# power.net
KiCad netlist of a schematic drawn in Altium Designer
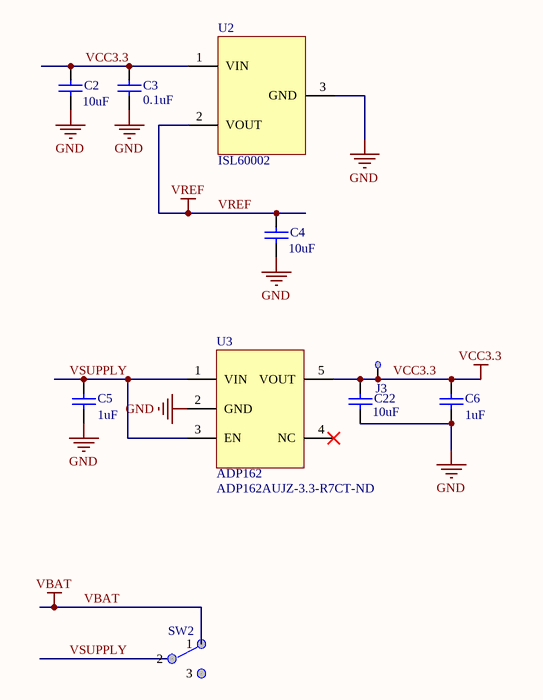
[diagram p0: power.SchDoc]

(export (version "E")
  (design (tool "Eeschema 10.0.6"))
  (components
    (comp (ref "C2")
      (value "10uF")
      (footprint "1608[0603]")
      (description "Capacitor (Semiconductor SIM Model)")
      (fields (field (name "Comment") "Cap Semi") (field (name "PUBLISHER") "Altium Limited"))
      (libsource (lib "Miscellaneous Devices") (part "Cap Semi"))
    )
    (comp (ref "C3")
      (value "0.1uF")
      (footprint "1608[0603]")
      (description "Capacitor (Semiconductor SIM Model)")
      (fields (field (name "Comment") "Cap Semi") (field (name "PUBLISHER") "Altium Limited"))
      (libsource (lib "Miscellaneous Devices") (part "Cap Semi"))
    )
    (comp (ref "C4")
      (value "10uF")
      (footprint "1608[0603]")
      (description "Capacitor (Semiconductor SIM Model)")
      (fields (field (name "Comment") "Cap Semi") (field (name "PUBLISHER") "Altium Limited"))
      (libsource (lib "Miscellaneous Devices") (part "Cap Semi"))
    )
    (comp (ref "C5")
      (value "1uF")
      (footprint "1608[0603]")
      (description "Capacitor (Semiconductor SIM Model)")
      (fields (field (name "Comment") "Cap Semi") (field (name "PUBLISHER") "Altium Limited"))
      (libsource (lib "Miscellaneous Devices") (part "Cap Semi"))
    )
    (comp (ref "C6")
      (value "1uF")
      (footprint "1608[0603]")
      (description "Capacitor (Semiconductor SIM Model)")
      (fields (field (name "Comment") "Cap Semi") (field (name "PUBLISHER") "Altium Limited"))
      (libsource (lib "Miscellaneous Devices") (part "Cap Semi"))
    )
    (comp (ref "C22")
      (value "10uF")
      (footprint "1608[0603]")
      (description "Capacitor (Semiconductor SIM Model)")
      (fields (field (name "Comment") "Cap Semi") (field (name "PUBLISHER") "Altium Limited"))
      (libsource (lib "Miscellaneous Devices") (part "Cap Semi"))
    )
    (comp (ref "J3")
      (value "5004")
      (footprint "TestPoint")
      (description "TEST POINT PC MINI .040\"D YELLOW")
      (libsource (lib "ultrasounic") (part "TestPoint"))
    )
    (comp (ref "SW2")
      (value "EG1218")
      (footprint "Slide Switch SPDT")
      (description "Switch 3 Pos")
      (libsource (lib "ultrasounic") (part "EG1218"))
    )
    (comp (ref "U2")
      (value "ISL60002")
      (footprint "SOT23-3N")
      (description "Precision Low Power FGA? Voltage References")
      (libsource (lib "ultrasounic") (part "ISL60002"))
    )
    (comp (ref "U3")
      (value "ADP162")
      (footprint "TSOT23-5")
      (description "Ultralow Quiescent Current,  150 mA, CMOS Linear Regulators")
      (fields (field (name "SUPPLIER PART NUMBER 1") "ADP162AUJZ-3.3-R7CT-ND"))
      (libsource (lib "ultrasounic") (part "ADP162"))
    )
  )
  (nets
    (net (code "1") (name "/VSUPPLY") (class "Default")
      (node (ref "C5") (pin "2") (pinfunction "2_2") (pintype "passive"))
      (node (ref "SW2") (pin "2") (pinfunction "2_2") (pintype "passive"))
      (node (ref "U3") (pin "1") (pinfunction "VIN_1") (pintype "passive"))
      (node (ref "U3") (pin "3") (pinfunction "EN_3") (pintype "passive"))
    )
    (net (code "2") (name "GND") (class "Default")
      (node (ref "C2") (pin "1") (pinfunction "1_1") (pintype "passive"))
      (node (ref "C22") (pin "1") (pinfunction "1_1") (pintype "passive"))
      (node (ref "C3") (pin "1") (pinfunction "1_1") (pintype "passive"))
      (node (ref "C4") (pin "1") (pinfunction "1_1") (pintype "passive"))
      (node (ref "C5") (pin "1") (pinfunction "1_1") (pintype "passive"))
      (node (ref "C6") (pin "1") (pinfunction "1_1") (pintype "passive"))
      (node (ref "U2") (pin "3") (pinfunction "GND_3") (pintype "passive"))
      (node (ref "U3") (pin "2") (pinfunction "GND_2") (pintype "passive"))
    )
    (net (code "3") (name "VBAT") (class "Default")
      (node (ref "SW2") (pin "1") (pinfunction "1_1") (pintype "passive"))
    )
    (net (code "4") (name "VCC3.3") (class "Default")
      (node (ref "C2") (pin "2") (pinfunction "2_2") (pintype "passive"))
      (node (ref "C22") (pin "2") (pinfunction "2_2") (pintype "passive"))
      (node (ref "C3") (pin "2") (pinfunction "2_2") (pintype "passive"))
      (node (ref "C6") (pin "2") (pinfunction "2_2") (pintype "passive"))
      (node (ref "J3") (pin "1") (pinfunction "TB_1") (pintype "passive"))
      (node (ref "U2") (pin "1") (pinfunction "VIN_1") (pintype "passive"))
      (node (ref "U3") (pin "5") (pinfunction "VOUT_5") (pintype "passive"))
    )
    (net (code "5") (name "VREF") (class "Default")
      (node (ref "C4") (pin "2") (pinfunction "2_2") (pintype "passive"))
      (node (ref "U2") (pin "2") (pinfunction "VOUT_2") (pintype "passive"))
    )
    (net (code "6") (name "unconnected-(SW2-Pad3)") (class "Default")
      (node (ref "SW2") (pin "3") (pinfunction "3_3") (pintype "passive"))
    )
    (net (code "7") (name "unconnected-(U3-NC-Pad4)") (class "Default")
      (node (ref "U3") (pin "4") (pinfunction "NC_4") (pintype "passive+no_connect"))
    )
  )
)
